# Voltage_detect.net
KiCad netlist of a schematic drawn in Altium Designer
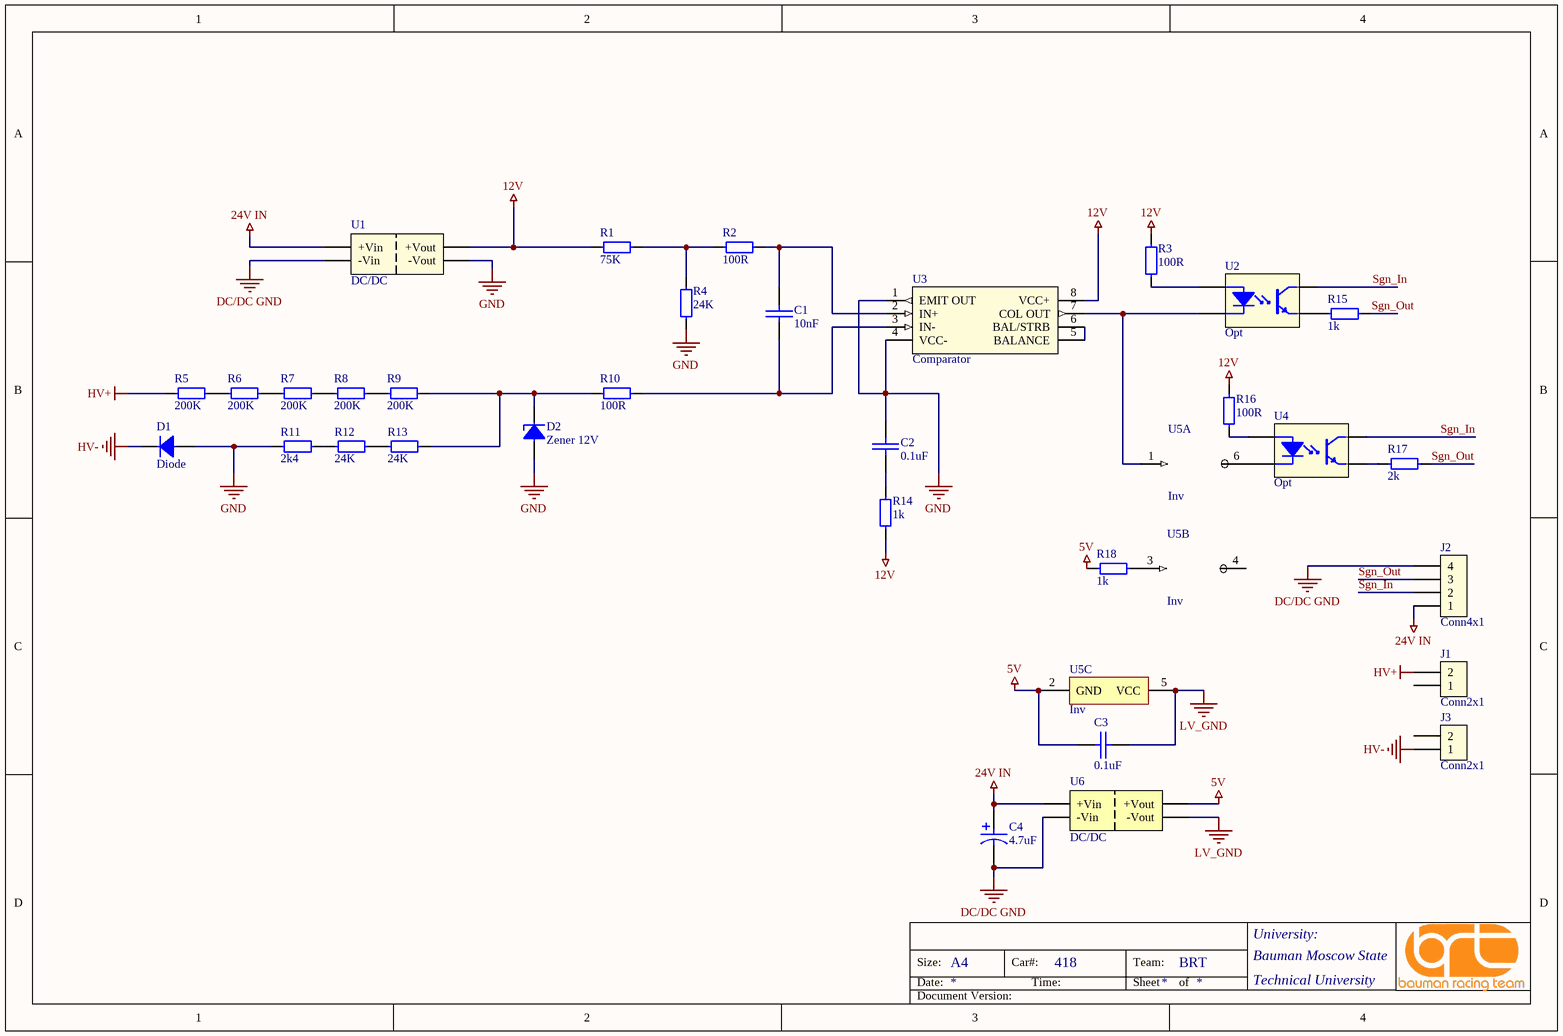
[diagram p0: Voltage detect.SchDoc]

(export (version "E")
  (design (tool "Eeschema 10.0.6"))
  (components
    (comp (ref "C1")
      (value "10nF")
      (footprint "0805 Capicator")
      (description "0805 X7R 10nF 100V 10%")
      (fields
        (field (name "MANUFACTURER") "Murata Manufacturing")
        (field (name "PART NUMBER") "GRM21BR72A103KA01L")
      )
      (libsource (lib "BRT_Components") (part "Cap 10nF (0805)"))
    )
    (comp (ref "C2")
      (value "0.1uF")
      (footprint "0805 Capicator")
      (description "0.1uF X7R 50V 10% 0805")
      (fields
        (field (name "MANUFACTURER") "Murata Manufacturing")
        (field (name "PART NUMBER") "GRM21BR71H104K")
      )
      (libsource (lib "BRT_Components") (part "Cap 0.1uF (0805)"))
    )
    (comp (ref "C3")
      (value "0.1uF")
      (footprint "0805 Capicator")
      (description "0.1uF X7R 50V 10% 0805")
      (fields
        (field (name "MANUFACTURER") "Murata Manufacturing")
        (field (name "PART NUMBER") "GRM21BR71E104KA01L")
      )
      (libsource (lib "BRT_Components") (part "Cap 0.1uF (0805)"))
    )
    (comp (ref "C4")
      (value "4.7uF")
      (footprint "Bar Cap 4x5.4")
      (description "ECAP SMD,  35V, 105°C")
      (fields (field (name "PART NUMBER") "B41121A7475M000") (field (name "MANUFACTURER") "Epcos"))
      (libsource (lib "BRT_Components") (part "Cap Pol 4.7uF"))
    )
    (comp (ref "D1")
      (value "Diode")
      (footprint "BY12")
      (description "BY12 - Highg voltage diode")
      (libsource (lib "TSAL_Lib") (part "BY12"))
    )
    (comp (ref "D2")
      (value "Zener 12V")
      (footprint "sod-323")
      (description "300mW")
      (fields (field (name "PART NUMBER") "BZX384-C12,115") (field (name "MANUFACTURER") "NXP Semiconductor"))
      (libsource (lib "BRT_Components") (part "Zener Diode 12V"))
    )
    (comp (ref "J1")
      (value "Conn2x1")
      (footprint "MolexMicroFit 2x1")
      (fields (field (name "PART NUMBER") "436500200") (field (name "MANUFACTURER") "Molex"))
      (libsource (lib "BRT_Components") (part "Conn2x1 [MicroFit]"))
    )
    (comp (ref "J2")
      (value "Conn4x1")
      (footprint "MolexMicroFit 4x1")
      (fields (field (name "PART NUMBER") "436500400") (field (name "MANUFACTURER") "Molex"))
      (libsource (lib "BRT_Components") (part "Conn4x1 [MicroFit]"))
    )
    (comp (ref "J3")
      (value "Conn2x1")
      (footprint "MolexMicroFit 2x1")
      (fields (field (name "PART NUMBER") "436500200") (field (name "MANUFACTURER") "Molex"))
      (libsource (lib "BRT_Components") (part "Conn2x1 [MicroFit]"))
    )
    (comp (ref "R1")
      (value "75K")
      (footprint "0805 Resistor")
      (description "0.125W 0805 75K, 1%")
      (fields (field (name "PART NUMBER") "RC0805FR-0775KL") (field (name "MANUFACTURER") "Taiwan"))
      (libsource (lib "PCB_Project") (part "Res 75K (0805)"))
    )
    (comp (ref "R2")
      (value "100R")
      (footprint "0805 Resistor")
      (description "0.125W 0805 100R, 1%")
      (fields (field (name "PART NUMBER") "RC0805FR-07100RL") (field (name "MANUFACTURER") "Taiwan"))
      (libsource (lib "BRT_Components") (part "Res 100R (0805)"))
    )
    (comp (ref "R3")
      (value "100R")
      (footprint "0805 Resistor")
      (description "0.125W 0805 100R, 1%")
      (fields (field (name "PART NUMBER") "RC0805FR-07100RL") (field (name "MANUFACTURER") "Taiwan"))
      (libsource (lib "BRT_Components") (part "Res 100R (0805)"))
    )
    (comp (ref "R4")
      (value "24K")
      (footprint "0805 Resistor")
      (description "0.125W 0805 24K, 1%")
      (fields (field (name "PART NUMBER") "RC0805FR-0724KL") (field (name "MANUFACTURER") "Taiwan"))
      (libsource (lib "PCB_Project") (part "Res 24K (0805)"))
    )
    (comp (ref "R5")
      (value "200K")
      (footprint "0805 Resistor")
      (description "0.125W 0805 200K, 1%")
      (fields (field (name "PART NUMBER") "RC0805FK-07200KL") (field (name "MANUFACTURER") "Taiwan"))
      (libsource (lib "PCB_Project") (part "Res 200K (0805)"))
    )
    (comp (ref "R6")
      (value "200K")
      (footprint "0805 Resistor")
      (description "0.125W 0805 200K, 1%")
      (fields (field (name "PART NUMBER") "RC0805FK-07200KL") (field (name "MANUFACTURER") "Taiwan"))
      (libsource (lib "PCB_Project") (part "Res 200K (0805)"))
    )
    (comp (ref "R7")
      (value "200K")
      (footprint "0805 Resistor")
      (description "0.125W 0805 200K, 1%")
      (fields (field (name "PART NUMBER") "RC0805FK-07200KL") (field (name "MANUFACTURER") "Taiwan"))
      (libsource (lib "PCB_Project") (part "Res 200K (0805)"))
    )
    (comp (ref "R8")
      (value "200K")
      (footprint "0805 Resistor")
      (description "0.125W 0805 200K, 1%")
      (fields (field (name "PART NUMBER") "RC0805FK-07200KL") (field (name "MANUFACTURER") "Taiwan"))
      (libsource (lib "PCB_Project") (part "Res 200K (0805)"))
    )
    (comp (ref "R9")
      (value "200K")
      (footprint "0805 Resistor")
      (description "0.125W 0805 200K, 1%")
      (fields (field (name "PART NUMBER") "RC0805FK-07200KL") (field (name "MANUFACTURER") "Taiwan"))
      (libsource (lib "PCB_Project") (part "Res 200K (0805)"))
    )
    (comp (ref "R10")
      (value "100R")
      (footprint "0805 Resistor")
      (description "0.125W 0805 100R, 1%")
      (fields (field (name "PART NUMBER") "RC0805FR-07100RL") (field (name "MANUFACTURER") "Taiwan"))
      (libsource (lib "BRT_Components") (part "Res 100R (0805)"))
    )
    (comp (ref "R11")
      (value "2k4")
      (footprint "0805 Resistor")
      (description "0.125W 0805 2.4k, 1%")
      (fields (field (name "PART NUMBER") "RC0805FR-072K4L") (field (name "MANUFACTURER") "Taiwan"))
      (libsource (lib "BRT_Components") (part "Res 2.4k (0805)"))
    )
    (comp (ref "R12")
      (value "24K")
      (footprint "0805 Resistor")
      (description "0.125W 0805 24K, 1%")
      (fields (field (name "PART NUMBER") "RC0805FR-0724KL") (field (name "MANUFACTURER") "Taiwan"))
      (libsource (lib "PCB_Project") (part "Res 24K (0805)"))
    )
    (comp (ref "R13")
      (value "24K")
      (footprint "0805 Resistor")
      (description "0.125W 0805 24K, 1%")
      (fields (field (name "PART NUMBER") "RC0805FR-0724KL") (field (name "MANUFACTURER") "Taiwan"))
      (libsource (lib "PCB_Project") (part "Res 24K (0805)"))
    )
    (comp (ref "R14")
      (value "1k")
      (footprint "0805 Resistor")
      (description "0.125W 0805 1k, 1%")
      (fields (field (name "PART NUMBER") "RC0805FR-071KL") (field (name "MANUFACTURER") "Taiwan"))
      (libsource (lib "BRT_Components") (part "Res 1k (0805)"))
    )
    (comp (ref "R15")
      (value "1k")
      (footprint "0603 Resistor")
      (description "0.1W 0603 1k, 1%")
      (fields (field (name "PART NUMBER") "RC0603FR-071KL") (field (name "MANUFACTURER") "Taiwan"))
      (libsource (lib "BRT_Components") (part "Res 1k (0603)"))
    )
    (comp (ref "R16")
      (value "100R")
      (footprint "0805 Resistor")
      (description "0.125W 0805 100R, 1%")
      (fields (field (name "PART NUMBER") "RC0805FR-07100RL") (field (name "MANUFACTURER") "Taiwan"))
      (libsource (lib "BRT_Components") (part "Res 100R (0805)"))
    )
    (comp (ref "R17")
      (value "2k")
      (footprint "0603 Resistor")
      (description "0.1W 0603 2k, 1%")
      (fields (field (name "PART NUMBER") "RC0603FR-072KL") (field (name "MANUFACTURER") "Taiwan"))
      (libsource (lib "BRT_Components") (part "Res 2k (0603)"))
    )
    (comp (ref "R18")
      (value "1k")
      (footprint "0805 Resistor")
      (description "0.125W 0805 1k, 1%")
      (fields (field (name "PART NUMBER") "RC0805FR-071KL") (field (name "MANUFACTURER") "Taiwan"))
      (libsource (lib "BRT_Components") (part "Res 1k (0805)"))
    )
    (comp (ref "U1")
      (value "DC/DC")
      (footprint "SIP7")
      (libsource (lib "PCB_Project") (part "DC/DC Isolated [TMH]"))
    )
    (comp (ref "U2")
      (value "Opt")
      (footprint "FAIR-MDIP-4_V")
      (fields (field (name "MANUFACTURER") "ON Semiconductor"))
      (libsource (lib "BRT_Components") (part "Optocoupler [FOD817B]"))
    )
    (comp (ref "U3")
      (value "Comparator")
      (footprint "SO-8")
      (description "Differential comparator with strobes")
      (fields (field (name "PART NUMBER") "LM311DR") (field (name "MANUFACTURER") "Texas Instruments"))
      (libsource (lib "BRT_Components") (part "Comparator [LM3]"))
    )
    (comp (ref "U4")
      (value "Opt")
      (footprint "FAIR-MDIP-4_V")
      (fields (field (name "MANUFACTURER") "ON Semiconductor"))
      (libsource (lib "") (part "Optocoupler [FOD817B]_1"))
    )
    (comp (ref "U5") (value "Inv") (footprint "SOT236") (libsource (lib "TSAL") (part "Inverter")))
    (comp (ref "U6")
      (value "DC/DC")
      (footprint "SIP7")
      (fields (field (name "MANUFACTURER") "Traco Power") (field (name "PART NUMBER") "TMH2405S"))
      (libsource (lib "BRT_Components") (part "DC/DC Isolated 5V [TMH]"))
    )
  )
  (nets
    (net (code "1") (name "/Sgn_In") (class "Default")
      (node (ref "J2") (pin "2") (pinfunction "2_2") (pintype "passive"))
      (node (ref "U2") (pin "4") (pinfunction "COLLECTOR_4") (pintype "passive"))
      (node (ref "U4") (pin "4") (pinfunction "COLLECTOR_4") (pintype "passive"))
    )
    (net (code "2") (name "/Sgn_Out") (class "Default")
      (node (ref "J2") (pin "3") (pinfunction "3_3") (pintype "passive"))
      (node (ref "R15") (pin "2") (pinfunction "2_2") (pintype "passive"))
      (node (ref "R17") (pin "2") (pinfunction "2_2") (pintype "passive"))
    )
    (net (code "3") (name "5V") (class "Default")
      (node (ref "C3") (pin "1") (pinfunction "1_1") (pintype "passive"))
      (node (ref "R18") (pin "2") (pinfunction "2_2") (pintype "passive"))
      (node (ref "U5") (pin "2") (pinfunction "GND_2") (pintype "passive"))
      (node (ref "U6") (pin "6") (pinfunction "+Vout_6") (pintype "power_in"))
    )
    (net (code "4") (name "12V") (class "Default")
      (node (ref "R1") (pin "1") (pinfunction "1_1") (pintype "passive"))
      (node (ref "R14") (pin "1") (pinfunction "1_1") (pintype "passive"))
      (node (ref "R16") (pin "2") (pinfunction "2_2") (pintype "passive"))
      (node (ref "R3") (pin "2") (pinfunction "2_2") (pintype "passive"))
      (node (ref "U1") (pin "6") (pinfunction "+Vout_6") (pintype "power_in"))
      (node (ref "U3") (pin "8") (pinfunction "VCC+_8") (pintype "power_in"))
    )
    (net (code "5") (name "24V IN") (class "Default")
      (node (ref "C4") (pin "2") (pinfunction "2_2") (pintype "passive"))
      (node (ref "J2") (pin "1") (pinfunction "1_1") (pintype "passive"))
      (node (ref "U1") (pin "1") (pinfunction "+Vin_1") (pintype "power_in"))
      (node (ref "U6") (pin "1") (pinfunction "+Vin_1") (pintype "power_in"))
    )
    (net (code "6") (name "DC{slash}DC GND") (class "Default")
      (node (ref "C4") (pin "1") (pinfunction "1_1") (pintype "passive"))
      (node (ref "J2") (pin "4") (pinfunction "4_4") (pintype "passive"))
      (node (ref "U1") (pin "2") (pinfunction "-Vin_2") (pintype "power_in"))
      (node (ref "U6") (pin "2") (pinfunction "-Vin_2") (pintype "power_in"))
    )
    (net (code "7") (name "GND") (class "Default")
      (node (ref "C2") (pin "2") (pinfunction "2_2") (pintype "passive"))
      (node (ref "D1") (pin "1") (pinfunction "1_1") (pintype "passive"))
      (node (ref "D2") (pin "1") (pinfunction "1_1") (pintype "passive"))
      (node (ref "R11") (pin "1") (pinfunction "1_1") (pintype "passive"))
      (node (ref "R4") (pin "1") (pinfunction "1_1") (pintype "passive"))
      (node (ref "U1") (pin "4") (pinfunction "-Vout_4") (pintype "power_in"))
      (node (ref "U3") (pin "1") (pinfunction "EMIT_OUT_1") (pintype "output"))
      (node (ref "U3") (pin "4") (pinfunction "VCC-_4") (pintype "power_in"))
    )
    (net (code "8") (name "HV+") (class "Default")
      (node (ref "J1") (pin "2") (pinfunction "2_2") (pintype "passive"))
      (node (ref "R5") (pin "1") (pinfunction "1_1") (pintype "passive"))
    )
    (net (code "9") (name "HV-") (class "Default")
      (node (ref "D1") (pin "2") (pinfunction "2_2") (pintype "passive"))
      (node (ref "J3") (pin "1") (pinfunction "1_1") (pintype "passive"))
    )
    (net (code "10") (name "LV_GND") (class "Default")
      (node (ref "C3") (pin "2") (pinfunction "2_2") (pintype "passive"))
      (node (ref "U5") (pin "5") (pinfunction "VCC_5") (pintype "passive"))
      (node (ref "U6") (pin "4") (pinfunction "-Vout_4") (pintype "power_in"))
    )
    (net (code "11") (name "Net-(C2-Pad1)") (class "Default")
      (node (ref "C2") (pin "1") (pinfunction "1_1") (pintype "passive"))
      (node (ref "R14") (pin "2") (pinfunction "2_2") (pintype "passive"))
    )
    (net (code "12") (name "Net-(D2-Pad2)") (class "Default")
      (node (ref "D2") (pin "2") (pinfunction "2_2") (pintype "passive"))
      (node (ref "R10") (pin "1") (pinfunction "1_1") (pintype "passive"))
      (node (ref "R13") (pin "2") (pinfunction "2_2") (pintype "passive"))
      (node (ref "R9") (pin "2") (pinfunction "2_2") (pintype "passive"))
    )
    (net (code "13") (name "Net-(R1-Pad2)") (class "Default")
      (node (ref "R1") (pin "2") (pinfunction "2_2") (pintype "passive"))
      (node (ref "R2") (pin "1") (pinfunction "1_1") (pintype "passive"))
      (node (ref "R4") (pin "2") (pinfunction "2_2") (pintype "passive"))
    )
    (net (code "14") (name "Net-(R5-Pad2)") (class "Default")
      (node (ref "R5") (pin "2") (pinfunction "2_2") (pintype "passive"))
      (node (ref "R6") (pin "1") (pinfunction "1_1") (pintype "passive"))
    )
    (net (code "15") (name "Net-(R6-Pad2)") (class "Default")
      (node (ref "R6") (pin "2") (pinfunction "2_2") (pintype "passive"))
      (node (ref "R7") (pin "1") (pinfunction "1_1") (pintype "passive"))
    )
    (net (code "16") (name "Net-(R7-Pad2)") (class "Default")
      (node (ref "R7") (pin "2") (pinfunction "2_2") (pintype "passive"))
      (node (ref "R8") (pin "1") (pinfunction "1_1") (pintype "passive"))
    )
    (net (code "17") (name "Net-(R8-Pad2)") (class "Default")
      (node (ref "R8") (pin "2") (pinfunction "2_2") (pintype "passive"))
      (node (ref "R9") (pin "1") (pinfunction "1_1") (pintype "passive"))
    )
    (net (code "18") (name "Net-(R11-Pad2)") (class "Default")
      (node (ref "R11") (pin "2") (pinfunction "2_2") (pintype "passive"))
      (node (ref "R12") (pin "2") (pinfunction "2_2") (pintype "passive"))
    )
    (net (code "19") (name "Net-(R12-Pad1)") (class "Default")
      (node (ref "R12") (pin "1") (pinfunction "1_1") (pintype "passive"))
      (node (ref "R13") (pin "1") (pinfunction "1_1") (pintype "passive"))
    )
    (net (code "20") (name "Net-(U2-ANODE)") (class "Default")
      (node (ref "R3") (pin "1") (pinfunction "1_1") (pintype "passive"))
      (node (ref "U2") (pin "1") (pinfunction "ANODE_1") (pintype "passive"))
    )
    (net (code "21") (name "Net-(U2-CATHODE)") (class "Default")
      (node (ref "U2") (pin "2") (pinfunction "CATHODE_2") (pintype "passive"))
      (node (ref "U3") (pin "7") (pinfunction "COL_OUT_7") (pintype "output"))
      (node (ref "U5") (pin "1") (pinfunction "A_1") (pintype "input"))
    )
    (net (code "22") (name "Net-(U2-EMITTER)") (class "Default")
      (node (ref "R15") (pin "1") (pinfunction "1_1") (pintype "passive"))
      (node (ref "U2") (pin "3") (pinfunction "EMITTER_3") (pintype "passive"))
    )
    (net (code "23") (name "Net-(U3-BALANCE)") (class "Default")
      (node (ref "U3") (pin "5") (pinfunction "BALANCE_5") (pintype "open_collector"))
      (node (ref "U3") (pin "6") (pinfunction "BAL/STRB_6") (pintype "open_collector"))
    )
    (net (code "24") (name "Net-(U3-IN+)") (class "Default")
      (node (ref "C1") (pin "2") (pinfunction "2_2") (pintype "passive"))
      (node (ref "R2") (pin "2") (pinfunction "2_2") (pintype "passive"))
      (node (ref "U3") (pin "2") (pinfunction "IN+_2") (pintype "input"))
    )
    (net (code "25") (name "Net-(U3-IN-)") (class "Default")
      (node (ref "C1") (pin "1") (pinfunction "1_1") (pintype "passive"))
      (node (ref "R10") (pin "2") (pinfunction "2_2") (pintype "passive"))
      (node (ref "U3") (pin "3") (pinfunction "IN-_3") (pintype "input"))
    )
    (net (code "26") (name "Net-(U4-ANODE)") (class "Default")
      (node (ref "R16") (pin "1") (pinfunction "1_1") (pintype "passive"))
      (node (ref "U4") (pin "1") (pinfunction "ANODE_1") (pintype "passive"))
    )
    (net (code "27") (name "Net-(U4-CATHODE)") (class "Default")
      (node (ref "U4") (pin "2") (pinfunction "CATHODE_2") (pintype "passive"))
      (node (ref "U5") (pin "6") (pinfunction "Y_6") (pintype "passive"))
    )
    (net (code "28") (name "Net-(U4-EMITTER)") (class "Default")
      (node (ref "R17") (pin "1") (pinfunction "1_1") (pintype "passive"))
      (node (ref "U4") (pin "3") (pinfunction "EMITTER_3") (pintype "passive"))
    )
    (net (code "29") (name "Net-(U5B-A)") (class "Default")
      (node (ref "R18") (pin "1") (pinfunction "1_1") (pintype "passive"))
      (node (ref "U5") (pin "3") (pinfunction "A_3") (pintype "input"))
    )
    (net (code "30") (name "unconnected-(J1-Pad1)") (class "Default")
      (node (ref "J1") (pin "1") (pinfunction "1_1") (pintype "passive"))
    )
    (net (code "31") (name "unconnected-(J3-Pad2)") (class "Default")
      (node (ref "J3") (pin "2") (pinfunction "2_2") (pintype "passive"))
    )
    (net (code "32") (name "unconnected-(U5B-Y-Pad4)") (class "Default")
      (node (ref "U5") (pin "4") (pinfunction "Y_4") (pintype "passive"))
    )
  )
)
